# Main_Board_ESP32.net
KiCad netlist of a schematic drawn in Altium Designer
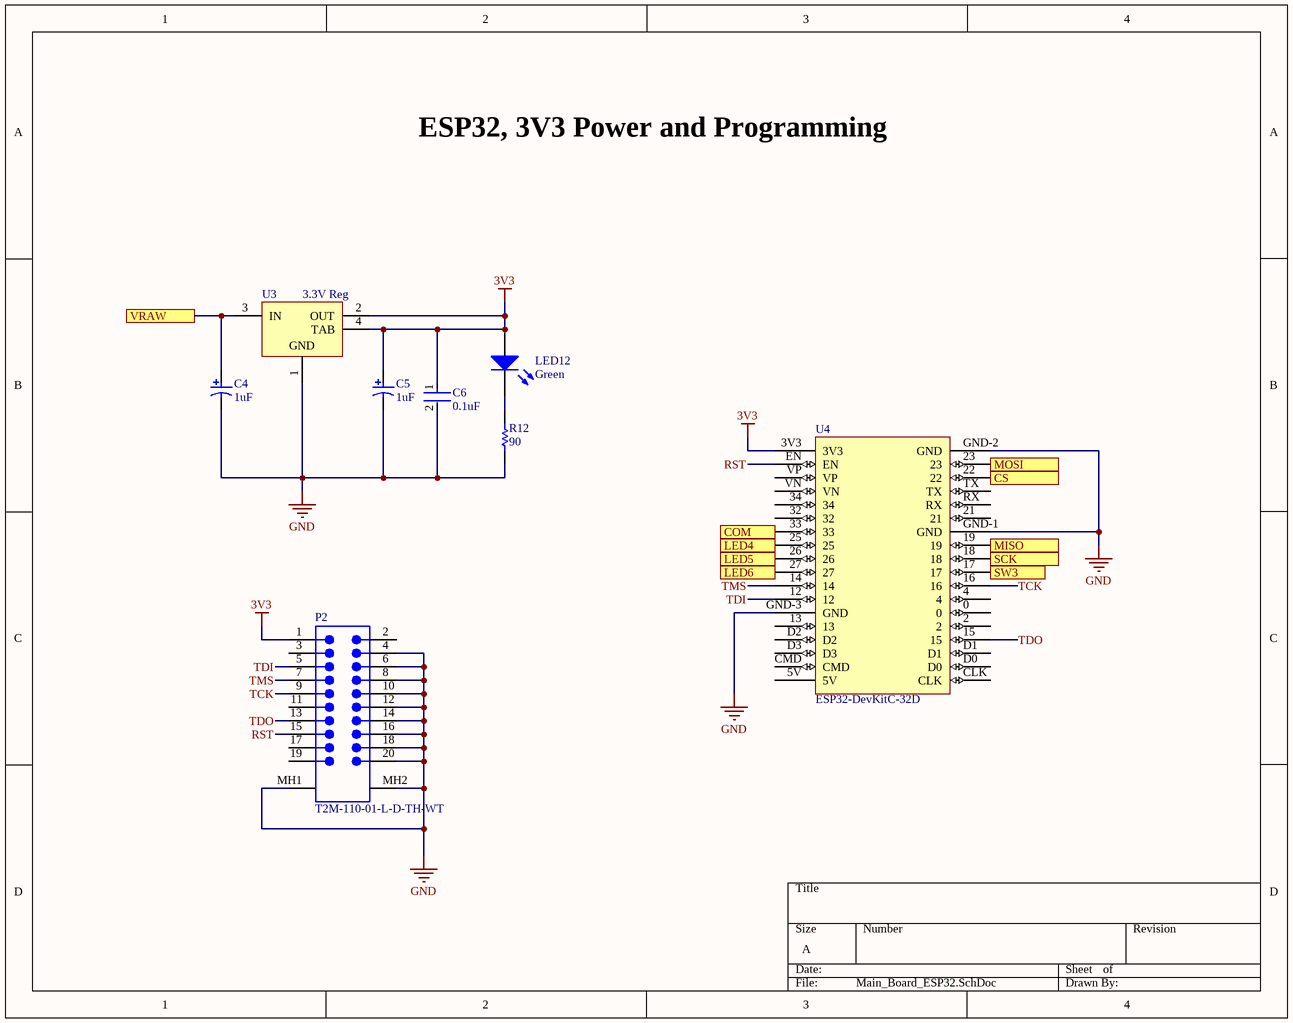
[diagram p0: Main_Board_ESP32.SchDoc]

(export (version "E")
  (design (tool "Eeschema 10.0.6"))
  (components
    (comp (ref "C4")
      (value "1uF")
      (footprint "KEMT-T491-C_L")
      (description "Tantalum Capacitor, 1 uF, +/- 10%, 50 V, -55 to 125 degC, 2-Pin SMD, RoHS, Tape and Reel")
      (fields (field (name "VOLTAGE") "50VDC") (field (name "MANUFACTURER") "Kemet"))
      (libsource (lib "Altium Content Vault") (part "CAP-P-2"))
    )
    (comp (ref "C5")
      (value "1uF")
      (footprint "KEMT-T491-C_L")
      (description "Tantalum Capacitor, 1 uF, +/- 10%, 50 V, -55 to 125 degC, 2-Pin SMD, RoHS, Tape and Reel")
      (fields (field (name "VOLTAGE") "50VDC") (field (name "MANUFACTURER") "Kemet"))
      (libsource (lib "Altium Content Vault") (part "CAP-P-2"))
    )
    (comp (ref "C6")
      (value "0.1uF")
      (footprint "FP-GCM188-0_1-IPC_B")
      (description "Ceramic Capacitor for Automotive 100nF  ±10% 50VDC X8L 0603 Paper T/R")
      (fields (field (name "TOLERANCE") "10%") (field (name "VOLTAGE") "50V"))
      (libsource (lib "Altium Content Vault") (part "02cd4be3c70576c341d710602a673aa"))
    )
    (comp (ref "LED12")
      (value "Green")
      (footprint "0603_A")
      (description "SMD mono-color Chip LED, WL-SMCW, Green")
      (fields (field (name "PARTNUMBER") "150060GS75000") (field (name "MANUFACTURER") "Wuerth Elektronik"))
      (libsource (lib "Altium Content Vault") (part "WE-LED_K1A2-2"))
    )
    (comp (ref "P2")
      (value "T2M-110-01-L-D-TH-WT")
      (footprint "SMTC-T2M-110-01-X-D-TH-WT")
      (fields (field (name "MANUFACTURER") "Samtec"))
      (libsource (lib "Altium Content Vault") (part "SMTC-T2M-110-01-X-D-WT"))
    )
    (comp (ref "R12")
      (value "90")
      (footprint "RESC2013X50X40LL20T20")
      (fields (field (name "MANUFACTURER") "Susumu") (field (name "PART NUMBER") "RR1220P-331-D"))
      (libsource (lib "Altium Content Vault") (part "RES"))
    )
    (comp (ref "U3")
      (value "3.3V Reg")
      (footprint "KTT0003B_N")
      (description "800mA Low-Dropout Linear Regulator, 3-pin TO-263, Pb-Free")
      (fields
        (field (name "PARTNUMBER") "LM1117SX-3.3/NOPB")
        (field (name "MANUFACTURER") "Texas Instruments")
      )
      (libsource (lib "Altium Content Vault") (part "PM-REG-LM1086-SOT4"))
    )
    (comp (ref "U4")
      (value "ESP32-DevKitC-32D")
      (footprint "ESP32-DevKitC-32D")
      (libsource (lib "SDP21_Main_Board_Schematic_Library") (part "ESP32-DevKitC-32D"))
    )
  )
  (nets
    (net (code "1") (name "/COM") (class "Default")
      (node (ref "U4") (pin "33") (pinfunction "33_33") (pintype "bidirectional"))
    )
    (net (code "2") (name "/CS") (class "Default")
      (node (ref "U4") (pin "22") (pinfunction "22_22") (pintype "bidirectional"))
    )
    (net (code "3") (name "/LED4") (class "Default")
      (node (ref "U4") (pin "25") (pinfunction "25_25") (pintype "bidirectional"))
    )
    (net (code "4") (name "/LED5") (class "Default")
      (node (ref "U4") (pin "26") (pinfunction "26_26") (pintype "bidirectional"))
    )
    (net (code "5") (name "/LED6") (class "Default")
      (node (ref "U4") (pin "27") (pinfunction "27_27") (pintype "bidirectional"))
    )
    (net (code "6") (name "/MISO") (class "Default")
      (node (ref "U4") (pin "19") (pinfunction "19_19") (pintype "bidirectional"))
    )
    (net (code "7") (name "/MOSI") (class "Default")
      (node (ref "U4") (pin "23") (pinfunction "23_23") (pintype "bidirectional"))
    )
    (net (code "8") (name "/RST") (class "Default")
      (node (ref "P2") (pin "15") (pinfunction "15_15") (pintype "passive"))
      (node (ref "U4") (pin "EN") (pinfunction "EN_EN") (pintype "bidirectional"))
    )
    (net (code "9") (name "/SCK") (class "Default")
      (node (ref "U4") (pin "18") (pinfunction "18_18") (pintype "bidirectional"))
    )
    (net (code "10") (name "/SW3") (class "Default")
      (node (ref "U4") (pin "17") (pinfunction "17_17") (pintype "bidirectional"))
    )
    (net (code "11") (name "/TCK") (class "Default")
      (node (ref "P2") (pin "9") (pinfunction "9_9") (pintype "passive"))
      (node (ref "U4") (pin "16") (pinfunction "16_16") (pintype "bidirectional"))
    )
    (net (code "12") (name "/TDI") (class "Default")
      (node (ref "P2") (pin "5") (pinfunction "5_5") (pintype "passive"))
      (node (ref "U4") (pin "12") (pinfunction "12_12") (pintype "bidirectional"))
    )
    (net (code "13") (name "/TDO") (class "Default")
      (node (ref "P2") (pin "13") (pinfunction "13_13") (pintype "passive"))
      (node (ref "U4") (pin "15") (pinfunction "15_15") (pintype "bidirectional"))
    )
    (net (code "14") (name "/TMS") (class "Default")
      (node (ref "P2") (pin "7") (pinfunction "7_7") (pintype "passive"))
      (node (ref "U4") (pin "14") (pinfunction "14_14") (pintype "bidirectional"))
    )
    (net (code "15") (name "/VRAW") (class "Default")
      (node (ref "C4") (pin "1") (pinfunction "1_1") (pintype "passive"))
      (node (ref "U3") (pin "3") (pinfunction "IN_3") (pintype "power_in"))
    )
    (net (code "16") (name "3V3") (class "Default")
      (node (ref "C5") (pin "1") (pinfunction "1_1") (pintype "passive"))
      (node (ref "C6") (pin "1") (pinfunction "1_1") (pintype "passive"))
      (node (ref "LED12") (pin "2") (pinfunction "A_2") (pintype "passive"))
      (node (ref "P2") (pin "1") (pinfunction "1_1") (pintype "passive"))
      (node (ref "U3") (pin "2") (pinfunction "OUT_2") (pintype "power_in"))
      (node (ref "U3") (pin "4") (pinfunction "TAB_4") (pintype "power_in"))
      (node (ref "U4") (pin "3V3") (pinfunction "3V3_3V3") (pintype "power_in"))
    )
    (net (code "17") (name "GND") (class "Default")
      (node (ref "C4") (pin "2") (pinfunction "2_2") (pintype "passive"))
      (node (ref "C5") (pin "2") (pinfunction "2_2") (pintype "passive"))
      (node (ref "C6") (pin "2") (pinfunction "2_2") (pintype "passive"))
      (node (ref "P2") (pin "10") (pinfunction "10_10") (pintype "passive"))
      (node (ref "P2") (pin "12") (pinfunction "12_12") (pintype "passive"))
      (node (ref "P2") (pin "14") (pinfunction "14_14") (pintype "passive"))
      (node (ref "P2") (pin "16") (pinfunction "16_16") (pintype "passive"))
      (node (ref "P2") (pin "18") (pinfunction "18_18") (pintype "passive"))
      (node (ref "P2") (pin "20") (pinfunction "20_20") (pintype "passive"))
      (node (ref "P2") (pin "4") (pinfunction "4_4") (pintype "passive"))
      (node (ref "P2") (pin "6") (pinfunction "6_6") (pintype "passive"))
      (node (ref "P2") (pin "8") (pinfunction "8_8") (pintype "passive"))
      (node (ref "P2") (pin "MH1") (pinfunction "MH1_MH1") (pintype "passive"))
      (node (ref "P2") (pin "MH2") (pinfunction "MH2_MH2") (pintype "passive"))
      (node (ref "R12") (pin "1") (pinfunction "1_1") (pintype "passive"))
      (node (ref "U3") (pin "1") (pinfunction "GND_1") (pintype "power_in"))
      (node (ref "U4") (pin "GND-1") (pinfunction "GND_GND-1") (pintype "power_in"))
      (node (ref "U4") (pin "GND-2") (pinfunction "GND_GND-2") (pintype "power_in"))
      (node (ref "U4") (pin "GND-3") (pinfunction "GND_GND-3") (pintype "power_in"))
    )
    (net (code "18") (name "Net-(LED12-K)") (class "Default")
      (node (ref "LED12") (pin "1") (pinfunction "K_1") (pintype "passive"))
      (node (ref "R12") (pin "2") (pinfunction "2_2") (pintype "passive"))
    )
    (net (code "19") (name "unconnected-(P2-Pad2)") (class "Default")
      (node (ref "P2") (pin "2") (pinfunction "2_2") (pintype "passive"))
    )
    (net (code "20") (name "unconnected-(P2-Pad3)") (class "Default")
      (node (ref "P2") (pin "3") (pinfunction "3_3") (pintype "passive"))
    )
    (net (code "21") (name "unconnected-(P2-Pad11)") (class "Default")
      (node (ref "P2") (pin "11") (pinfunction "11_11") (pintype "passive"))
    )
    (net (code "22") (name "unconnected-(P2-Pad17)") (class "Default")
      (node (ref "P2") (pin "17") (pinfunction "17_17") (pintype "passive"))
    )
    (net (code "23") (name "unconnected-(P2-Pad19)") (class "Default")
      (node (ref "P2") (pin "19") (pinfunction "19_19") (pintype "passive"))
    )
    (net (code "24") (name "unconnected-(U4-Pad0)") (class "Default")
      (node (ref "U4") (pin "0") (pinfunction "0_0") (pintype "bidirectional"))
    )
    (net (code "25") (name "unconnected-(U4-Pad2)") (class "Default")
      (node (ref "U4") (pin "2") (pinfunction "2_2") (pintype "bidirectional"))
    )
    (net (code "26") (name "unconnected-(U4-Pad4)") (class "Default")
      (node (ref "U4") (pin "4") (pinfunction "4_4") (pintype "bidirectional"))
    )
    (net (code "27") (name "unconnected-(U4-Pad5V)") (class "Default")
      (node (ref "U4") (pin "5V") (pinfunction "5V_5V") (pintype "power_in"))
    )
    (net (code "28") (name "unconnected-(U4-Pad13)") (class "Default")
      (node (ref "U4") (pin "13") (pinfunction "13_13") (pintype "bidirectional"))
    )
    (net (code "29") (name "unconnected-(U4-Pad21)") (class "Default")
      (node (ref "U4") (pin "21") (pinfunction "21_21") (pintype "bidirectional"))
    )
    (net (code "30") (name "unconnected-(U4-Pad32)") (class "Default")
      (node (ref "U4") (pin "32") (pinfunction "32_32") (pintype "bidirectional"))
    )
    (net (code "31") (name "unconnected-(U4-Pad34)") (class "Default")
      (node (ref "U4") (pin "34") (pinfunction "34_34") (pintype "bidirectional"))
    )
    (net (code "32") (name "unconnected-(U4-PadCLK)") (class "Default")
      (node (ref "U4") (pin "CLK") (pinfunction "CLK_CLK") (pintype "bidirectional"))
    )
    (net (code "33") (name "unconnected-(U4-PadCMD)") (class "Default")
      (node (ref "U4") (pin "CMD") (pinfunction "CMD_CMD") (pintype "bidirectional"))
    )
    (net (code "34") (name "unconnected-(U4-PadD0)") (class "Default")
      (node (ref "U4") (pin "D0") (pinfunction "D0_D0") (pintype "bidirectional"))
    )
    (net (code "35") (name "unconnected-(U4-PadD1)") (class "Default")
      (node (ref "U4") (pin "D1") (pinfunction "D1_D1") (pintype "bidirectional"))
    )
    (net (code "36") (name "unconnected-(U4-PadD2)") (class "Default")
      (node (ref "U4") (pin "D2") (pinfunction "D2_D2") (pintype "bidirectional"))
    )
    (net (code "37") (name "unconnected-(U4-PadD3)") (class "Default")
      (node (ref "U4") (pin "D3") (pinfunction "D3_D3") (pintype "bidirectional"))
    )
    (net (code "38") (name "unconnected-(U4-PadRX)") (class "Default")
      (node (ref "U4") (pin "RX") (pinfunction "RX_RX") (pintype "bidirectional"))
    )
    (net (code "39") (name "unconnected-(U4-PadTX)") (class "Default")
      (node (ref "U4") (pin "TX") (pinfunction "TX_TX") (pintype "bidirectional"))
    )
    (net (code "40") (name "unconnected-(U4-PadVN)") (class "Default")
      (node (ref "U4") (pin "VN") (pinfunction "VN_VN") (pintype "bidirectional"))
    )
    (net (code "41") (name "unconnected-(U4-PadVP)") (class "Default")
      (node (ref "U4") (pin "VP") (pinfunction "VP_VP") (pintype "bidirectional"))
    )
  )
)
